# T35_4_FX3.net
KiCad netlist of a schematic drawn in Altium Designer
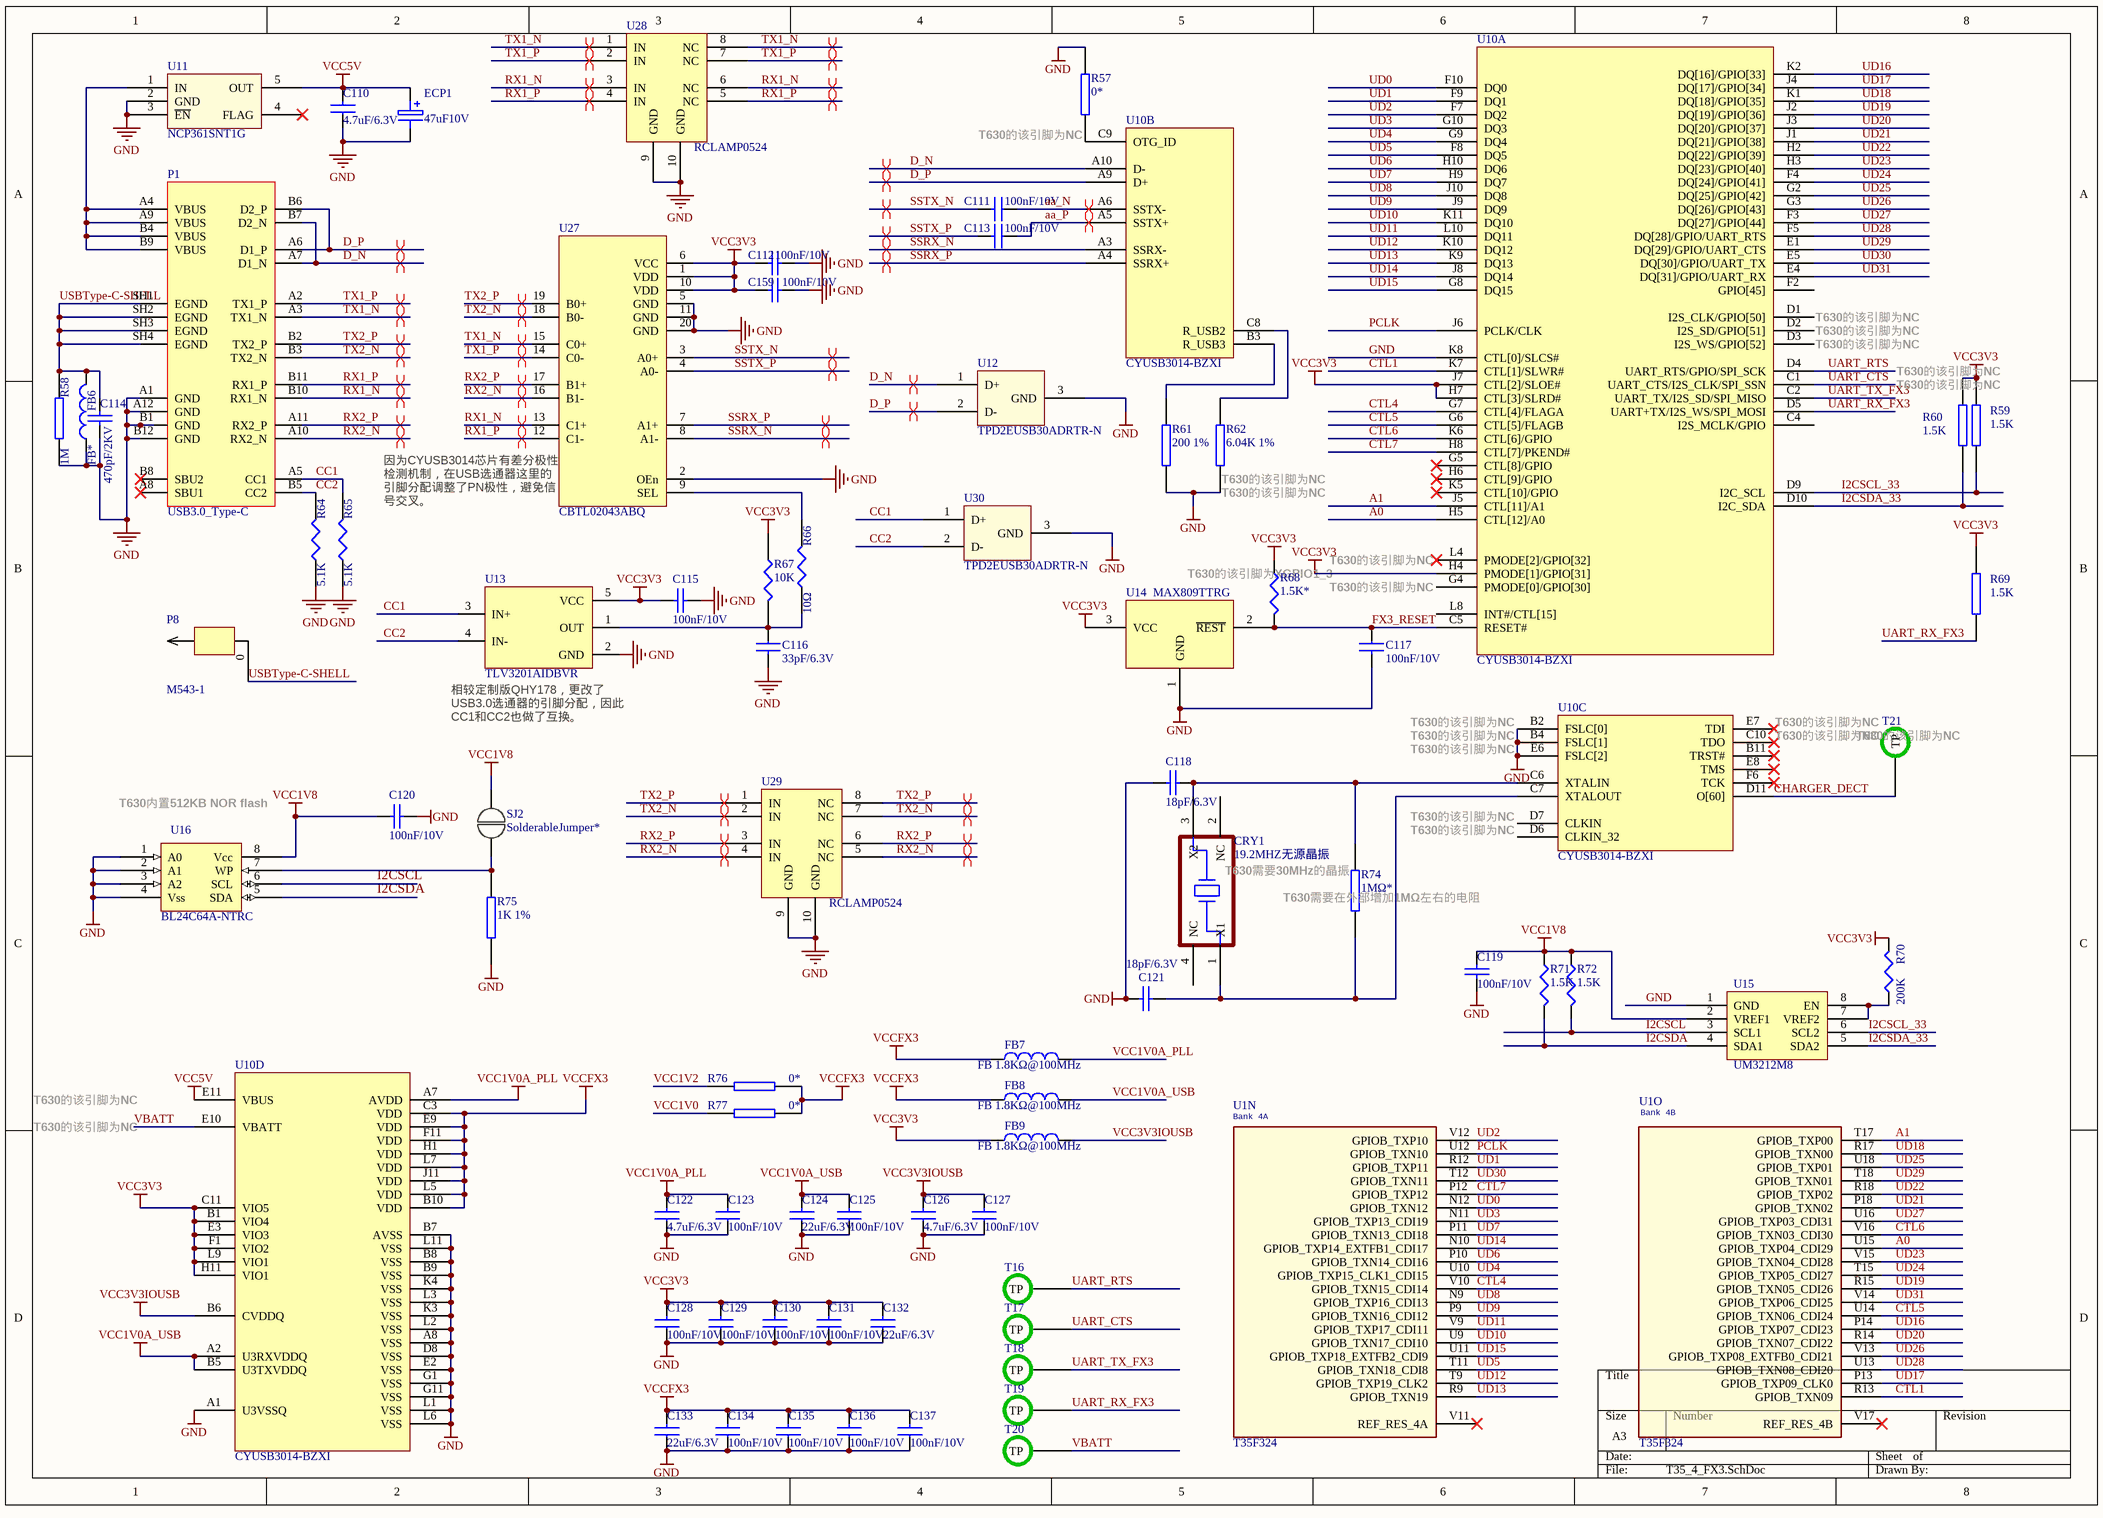
[diagram p0: T35_4_FX3.SchDoc]

(export (version "E")
  (design (tool "Eeschema 10.0.6"))
  (components
    (comp (ref "C110")
      (value "4.7uF/6.3V")
      (footprint "0402CS")
      (description "贴片电容")
      (libsource (lib "*") (part "CAPACITOR NON-POL"))
    )
    (comp (ref "C111")
      (value "100nF/10V")
      (footprint "0201CS")
      (description "贴片电容")
      (libsource (lib "*") (part "CAPACITOR NON-POL"))
    )
    (comp (ref "C112")
      (value "100nF/10V")
      (footprint "0201CS")
      (description "贴片电容")
      (libsource (lib "*") (part "CAP"))
    )
    (comp (ref "C113")
      (value "100nF/10V")
      (footprint "0201CS")
      (description "贴片电容")
      (libsource (lib "*") (part "CAPACITOR NON-POL"))
    )
    (comp (ref "C114")
      (value "470pF/2KV")
      (footprint "1206CS")
      (description "贴片电容")
      (libsource (lib "*") (part "CAP"))
    )
    (comp (ref "C115")
      (value "100nF/10V")
      (footprint "0201CS")
      (description "贴片电容")
      (libsource (lib "*") (part "CAP"))
    )
    (comp (ref "C116")
      (value "33pF/6.3V")
      (footprint "0402CS")
      (description "贴片电容")
      (libsource (lib "*") (part "CAPACITOR NON-POL"))
    )
    (comp (ref "C117")
      (value "100nF/10V")
      (footprint "0201CS")
      (description "贴片电容")
      (libsource (lib "*") (part "CAPACITOR NON-POL"))
    )
    (comp (ref "C118")
      (value "18pF/6.3V")
      (footprint "0201CS")
      (description "贴片电容")
      (libsource (lib "*") (part "CAP"))
    )
    (comp (ref "C119")
      (value "100nF/10V")
      (footprint "0201CS")
      (description "贴片电容")
      (libsource (lib "*") (part "CAP"))
    )
    (comp (ref "C120")
      (value "100nF/10V")
      (footprint "0201CS")
      (description "贴片电容")
      (libsource (lib "*") (part "CAP"))
    )
    (comp (ref "C121")
      (value "18pF/6.3V")
      (footprint "0201CS")
      (description "贴片电容")
      (libsource (lib "*") (part "CAP"))
    )
    (comp (ref "C122")
      (value "4.7uF/6.3V")
      (footprint "0402CS")
      (description "贴片电容")
      (libsource (lib "*") (part "CAPACITOR NON-POL"))
    )
    (comp (ref "C123")
      (value "100nF/10V")
      (footprint "0201CS")
      (description "贴片电容")
      (libsource (lib "*") (part "CAPACITOR NON-POL"))
    )
    (comp (ref "C124")
      (value "22uF/6.3V")
      (footprint "0603CS")
      (description "贴片电容")
      (libsource (lib "*") (part "CAPACITOR NON-POL"))
    )
    (comp (ref "C125")
      (value "100nF/10V")
      (footprint "0201CS")
      (description "贴片电容")
      (libsource (lib "*") (part "CAPACITOR NON-POL"))
    )
    (comp (ref "C126")
      (value "4.7uF/6.3V")
      (footprint "0402CS")
      (description "贴片电容")
      (libsource (lib "*") (part "CAPACITOR NON-POL"))
    )
    (comp (ref "C127")
      (value "100nF/10V")
      (footprint "0201CS")
      (description "贴片电容")
      (libsource (lib "*") (part "CAPACITOR NON-POL"))
    )
    (comp (ref "C128")
      (value "100nF/10V")
      (footprint "0201CS")
      (description "贴片电容")
      (libsource (lib "*") (part "CAPACITOR NON-POL"))
    )
    (comp (ref "C129")
      (value "100nF/10V")
      (footprint "0201CS")
      (description "贴片电容")
      (libsource (lib "*") (part "CAPACITOR NON-POL"))
    )
    (comp (ref "C130")
      (value "100nF/10V")
      (footprint "0201CS")
      (description "贴片电容")
      (libsource (lib "*") (part "CAPACITOR NON-POL"))
    )
    (comp (ref "C131")
      (value "100nF/10V")
      (footprint "0201CS")
      (description "贴片电容")
      (libsource (lib "*") (part "CAPACITOR NON-POL"))
    )
    (comp (ref "C132")
      (value "22uF/6.3V")
      (footprint "0603CS")
      (description "贴片电容")
      (libsource (lib "*") (part "CAPACITOR NON-POL"))
    )
    (comp (ref "C133")
      (value "22uF/6.3V")
      (footprint "0603CS")
      (description "贴片电容")
      (libsource (lib "*") (part "CAPACITOR NON-POL"))
    )
    (comp (ref "C134")
      (value "100nF/10V")
      (footprint "0201CS")
      (description "贴片电容")
      (libsource (lib "*") (part "CAPACITOR NON-POL"))
    )
    (comp (ref "C135")
      (value "100nF/10V")
      (footprint "0201CS")
      (description "贴片电容")
      (libsource (lib "*") (part "CAPACITOR NON-POL"))
    )
    (comp (ref "C136")
      (value "100nF/10V")
      (footprint "0201CS")
      (description "贴片电容")
      (libsource (lib "*") (part "CAPACITOR NON-POL"))
    )
    (comp (ref "C137")
      (value "100nF/10V")
      (footprint "0201CS")
      (description "贴片电容")
      (libsource (lib "*") (part "CAPACITOR NON-POL"))
    )
    (comp (ref "C159")
      (value "100nF/10V")
      (footprint "0201CS")
      (description "贴片电容")
      (libsource (lib "*") (part "CAP"))
    )
    (comp (ref "CRY1")
      (value "19.2MHZ无源晶振")
      (footprint "XTAL_SMD_SMALL")
      (description "无源晶振")
      (libsource (lib "QHY_SCHLIB") (part "CRY-4S"))
    )
    (comp (ref "ECP1")
      (value "47uF10V")
      (footprint "CASE-B")
      (description "钽电容")
      (libsource (lib "QHY_LIB_SCH_AD10") (part "ELECTRO1"))
    )
    (comp (ref "FB6")
      (value "FB*")
      (footprint "FB0603")
      (description "贴片磁珠")
      (libsource (lib "QHY_LIB_SCH_AD10") (part "INDUCTOR"))
    )
    (comp (ref "FB7")
      (value "FB 1.8KΩ@100MHz")
      (footprint "FB0603")
      (description "贴片磁珠")
      (libsource (lib "Miscellaneous Devices") (part "Inductor"))
    )
    (comp (ref "FB8")
      (value "FB 1.8KΩ@100MHz")
      (footprint "FB0603")
      (description "贴片磁珠")
      (libsource (lib "Miscellaneous Devices") (part "Inductor"))
    )
    (comp (ref "FB9")
      (value "FB 1.8KΩ@100MHz")
      (footprint "FB0603")
      (description "贴片磁珠")
      (libsource (lib "Miscellaneous Devices") (part "Inductor"))
    )
    (comp (ref "P1")
      (value "USB3.0_Type-C")
      (footprint "CONN_105450-0101_MOL - duplicate")
      (description "USB Type-C连接器")
      (libsource (lib "IMX411_V1") (part "USB3.0_Type-C"))
    )
    (comp (ref "P8")
      (value "M543-1")
      (footprint "M543-1")
      (description "弹簧针")
      (libsource (lib "T35-V2") (part "M543-1"))
    )
    (comp (ref "R57")
      (value "0*")
      (footprint "0201RS")
      (description "贴片电阻")
      (libsource (lib "*") (part "RES2"))
    )
    (comp (ref "R58")
      (value "1M")
      (footprint "0603RS")
      (description "贴片电阻")
      (libsource (lib "") (part "RES2_1"))
    )
    (comp (ref "R59")
      (value "1.5K")
      (footprint "0402RS")
      (description "贴片电阻")
      (libsource (lib "*") (part "RES2"))
    )
    (comp (ref "R60")
      (value "1.5K")
      (footprint "0402RS")
      (description "贴片电阻")
      (libsource (lib "*") (part "RES2"))
    )
    (comp (ref "R61")
      (value "200 1%")
      (footprint "0402RS")
      (description "贴片电阻")
      (libsource (lib "") (part "RES2_1"))
    )
    (comp (ref "R62")
      (value "6.04K 1%")
      (footprint "0402RS")
      (description "贴片电阻")
      (libsource (lib "") (part "RES2_1"))
    )
    (comp (ref "R64")
      (value "5.1K")
      (footprint "0201RS")
      (description "贴片电阻")
      (libsource (lib "*") (part "RES1"))
    )
    (comp (ref "R65")
      (value "5.1K")
      (footprint "0201RS")
      (description "贴片电阻")
      (libsource (lib "*") (part "RES1"))
    )
    (comp (ref "R66")
      (value "10Ω")
      (footprint "0402RS")
      (description "贴片电阻")
      (libsource (lib "*") (part "RES1"))
    )
    (comp (ref "R67")
      (value "10K")
      (footprint "0201RS")
      (description "贴片电阻")
      (libsource (lib "*") (part "RES1"))
    )
    (comp (ref "R68")
      (value "1.5K*")
      (footprint "0402RS")
      (description "贴片电阻")
      (fields (field (name "PUBLISHER") "Altium Limited"))
      (libsource (lib "Miscellaneous Devices") (part "Res3"))
    )
    (comp (ref "R69")
      (value "1.5K")
      (footprint "0402RS")
      (description "贴片电阻")
      (libsource (lib "*") (part "RES2"))
    )
    (comp (ref "R70")
      (value "200K")
      (footprint "0201RS")
      (description "贴片电阻")
      (fields (field (name "PUBLISHER") "Altium Limited"))
      (libsource (lib "Miscellaneous Devices") (part "Res3"))
    )
    (comp (ref "R71")
      (value "1.5K")
      (footprint "0402RS")
      (description "贴片电阻")
      (fields (field (name "PUBLISHER") "Altium Limited"))
      (libsource (lib "Miscellaneous Devices") (part "Res3"))
    )
    (comp (ref "R72")
      (value "1.5K")
      (footprint "0402RS")
      (description "贴片电阻")
      (fields (field (name "PUBLISHER") "Altium Limited"))
      (libsource (lib "Miscellaneous Devices") (part "Res3"))
    )
    (comp (ref "R74")
      (value "1MΩ*")
      (footprint "0402RS")
      (description "贴片电阻")
      (libsource (lib "") (part "RES2_1"))
    )
    (comp (ref "R75")
      (value "1K 1%")
      (footprint "0402RS")
      (description "贴片电阻")
      (libsource (lib "") (part "RES2_1"))
    )
    (comp (ref "R76")
      (value "0*")
      (footprint "0402RS")
      (description "贴片电阻")
      (libsource (lib "") (part "RES2_1"))
    )
    (comp (ref "R77")
      (value "0*")
      (footprint "0402RS")
      (description "贴片电阻")
      (libsource (lib "") (part "RES2_1"))
    )
    (comp (ref "SJ2")
      (value "SolderableJumper*")
      (footprint "SJ")
      (libsource (lib "T35-V2") (part "SolderableJumper"))
    )
    (comp (ref "T16")
      (value "~")
      (footprint "TP-S")
      (description "测试点")
      (libsource (lib "QHY_SCHLIB") (part "TP"))
    )
    (comp (ref "T17")
      (value "~")
      (footprint "TP-S")
      (description "测试点")
      (libsource (lib "QHY_SCHLIB") (part "TP"))
    )
    (comp (ref "T18")
      (value "~")
      (footprint "TP-S")
      (description "测试点")
      (libsource (lib "QHY_SCHLIB") (part "TP"))
    )
    (comp (ref "T19")
      (value "~")
      (footprint "TP-S")
      (description "测试点")
      (libsource (lib "QHY_SCHLIB") (part "TP"))
    )
    (comp (ref "T20")
      (value "~")
      (footprint "TP-S")
      (description "测试点")
      (libsource (lib "QHY_SCHLIB") (part "TP"))
    )
    (comp (ref "T21")
      (value "~")
      (footprint "TP-S")
      (description "测试点")
      (libsource (lib "QHY_SCHLIB") (part "TP"))
    )
    (comp (ref "U1")
      (value "T35F324")
      (footprint "T35-F324-BGA100P9X9-81A")
      (description "FPGA芯片")
      (libsource (lib "orcadt35-v1.0_Library") (part "T35F324"))
    )
    (comp (ref "U10")
      (value "CYUSB3014-BZXI")
      (footprint "CYUSB3014")
      (description "FX3芯片")
      (libsource (lib "QHY_SCHLIB") (part "CYUSB3014"))
    )
    (comp (ref "U11")
      (value "NCP361SNT1G")
      (footprint "SOT-23-5")
      (description "USB过压过流保护芯片")
      (libsource (lib "T35-V2") (part "NCP361SNT1G"))
    )
    (comp (ref "U12")
      (value "TPD2EUSB30ADRTR-N")
      (footprint "DRT0003A")
      (description "ESD保护器件")
      (libsource (lib "T35-V2") (part "TPD2EUSB30ADRTR-N"))
    )
    (comp (ref "U13")
      (value "TLV3201AIDBVR")
      (footprint "sot-23-5")
      (description "比较器")
      (libsource (lib "IMX411_V1") (part "TLV3201AIDBVR"))
    )
    (comp (ref "U14")
      (value "MAX809TTRG")
      (footprint "MAX809")
      (description "复位芯片")
      (libsource (lib "QHY_SCHLIB") (part "MAX809"))
    )
    (comp (ref "U15")
      (value "UM3212M8")
      (footprint "MSOP8")
      (description "I2C电平转换芯片")
      (libsource (lib "QHY_LIB_SCH_AD10") (part "UM3212M8"))
    )
    (comp (ref "U16")
      (value "BL24C64A-NTRC")
      (footprint "UDFN-8LL")
      (description "EEPROM芯片")
      (libsource (lib "*") (part "24LC00"))
    )
    (comp (ref "U27")
      (value "CBTL02043ABQ")
      (footprint "VQFN-20")
      (description "USB3.0选通芯片")
      (libsource (lib "T35-V2") (part "CBTL02043ABQ"))
    )
    (comp (ref "U28")
      (value "RCLAMP0524")
      (footprint "RCLAMP0524")
      (description "ESD保护器件")
      (libsource (lib "QHY_SCHLIB") (part "RCLAMP0524"))
    )
    (comp (ref "U29")
      (value "RCLAMP0524")
      (footprint "RCLAMP0524")
      (description "ESD保护器件")
      (libsource (lib "QHY_SCHLIB") (part "RCLAMP0524"))
    )
    (comp (ref "U30")
      (value "TPD2EUSB30ADRTR-N")
      (footprint "DRT0003A")
      (description "ESD保护器件")
      (libsource (lib "T35-V2") (part "TPD2EUSB30ADRTR-N"))
    )
  )
  (nets
    (net (code "1") (name "/A0") (class "Default")
      (node (ref "U1") (pin "U15") (pinfunction "GPIOB_TXP04_CDI29_U15") (pintype "power_in"))
      (node (ref "U10") (pin "H5") (pinfunction "CTL[12]/A0_H5") (pintype "passive"))
    )
    (net (code "2") (name "/A1") (class "Default")
      (node (ref "U1") (pin "T17") (pinfunction "GPIOB_TXP00_T17") (pintype "power_in"))
      (node (ref "U10") (pin "J5") (pinfunction "CTL[11]/A1_J5") (pintype "passive"))
    )
    (net (code "3") (name "/CC1") (class "Default")
      (node (ref "P1") (pin "A5") (pinfunction "CC1_A5") (pintype "passive"))
      (node (ref "R65") (pin "2") (pinfunction "2_2") (pintype "passive"))
      (node (ref "U13") (pin "3") (pinfunction "IN+_3") (pintype "passive"))
      (node (ref "U30") (pin "1") (pinfunction "D+_1") (pintype "passive"))
    )
    (net (code "4") (name "/CC2") (class "Default")
      (node (ref "P1") (pin "B5") (pinfunction "CC2_B5") (pintype "passive"))
      (node (ref "R64") (pin "2") (pinfunction "2_2") (pintype "passive"))
      (node (ref "U13") (pin "4") (pinfunction "IN-_4") (pintype "passive"))
      (node (ref "U30") (pin "2") (pinfunction "D-_2") (pintype "passive"))
    )
    (net (code "5") (name "/CHARGER_DECT") (class "Default")
      (node (ref "T21") (pin "1") (pinfunction "TP_1") (pintype "passive"))
      (node (ref "U10") (pin "D11") (pinfunction "O[60]_D11") (pintype "passive"))
    )
    (net (code "6") (name "/CTL1") (class "Default")
      (node (ref "U1") (pin "R13") (pinfunction "GPIOB_TXN09_R13") (pintype "power_in"))
      (node (ref "U10") (pin "K7") (pinfunction "CTL[1]/SLWR#_K7") (pintype "passive"))
    )
    (net (code "7") (name "/CTL4") (class "Default")
      (node (ref "U1") (pin "V10") (pinfunction "GPIOB_TXN15_CDI14_V10") (pintype "passive"))
      (node (ref "U10") (pin "G7") (pinfunction "CTL[4]/FLAGA_G7") (pintype "passive"))
    )
    (net (code "8") (name "/CTL5") (class "Default")
      (node (ref "U1") (pin "U14") (pinfunction "GPIOB_TXN06_CDI24_U14") (pintype "power_in"))
      (node (ref "U10") (pin "G6") (pinfunction "CTL[5]/FLAGB_G6") (pintype "passive"))
    )
    (net (code "9") (name "/CTL6") (class "Default")
      (node (ref "U1") (pin "V16") (pinfunction "GPIOB_TXN03_CDI30_V16") (pintype "power_in"))
      (node (ref "U10") (pin "K6") (pinfunction "CTL[6]/GPIO_K6") (pintype "passive"))
    )
    (net (code "10") (name "/CTL7") (class "Default")
      (node (ref "U1") (pin "P12") (pinfunction "GPIOB_TXP12_P12") (pintype "passive"))
      (node (ref "U10") (pin "H8") (pinfunction "CTL[7]/PKEND#_H8") (pintype "passive"))
    )
    (net (code "11") (name "/D_N") (class "Default")
      (node (ref "P1") (pin "A7") (pinfunction "D1_N_A7") (pintype "passive"))
      (node (ref "P1") (pin "B7") (pinfunction "D2_N_B7") (pintype "passive"))
      (node (ref "U10") (pin "A10") (pinfunction "D-_A10") (pintype "passive"))
      (node (ref "U12") (pin "1") (pinfunction "D+_1") (pintype "passive"))
    )
    (net (code "12") (name "/D_P") (class "Default")
      (node (ref "P1") (pin "A6") (pinfunction "D1_P_A6") (pintype "passive"))
      (node (ref "P1") (pin "B6") (pinfunction "D2_P_B6") (pintype "passive"))
      (node (ref "U10") (pin "A9") (pinfunction "D+_A9") (pintype "passive"))
      (node (ref "U12") (pin "2") (pinfunction "D-_2") (pintype "passive"))
    )
    (net (code "13") (name "/FX3_RESET") (class "Default")
      (node (ref "C117") (pin "1") (pinfunction "1_1") (pintype "passive"))
      (node (ref "R68") (pin "2") (pinfunction "2_2") (pintype "passive"))
      (node (ref "U10") (pin "C5") (pinfunction "RESET#_C5") (pintype "passive"))
      (node (ref "U14") (pin "2") (pinfunction "~{REST}_2") (pintype "passive"))
    )
    (net (code "14") (name "/I2CSCL") (class "Default")
      (node (ref "R72") (pin "2") (pinfunction "2_2") (pintype "passive"))
      (node (ref "U15") (pin "3") (pinfunction "SCL1_3") (pintype "passive"))
      (node (ref "U16") (pin "6") (pinfunction "SCL_6") (pintype "bidirectional"))
    )
    (net (code "15") (name "/I2CSCL_33") (class "Default")
      (node (ref "R59") (pin "2") (pinfunction "2_2") (pintype "passive"))
      (node (ref "U10") (pin "D9") (pinfunction "I2C_SCL_D9") (pintype "passive"))
      (node (ref "U15") (pin "6") (pinfunction "SCL2_6") (pintype "passive"))
    )
    (net (code "16") (name "/I2CSDA") (class "Default")
      (node (ref "R71") (pin "2") (pinfunction "2_2") (pintype "passive"))
      (node (ref "U15") (pin "4") (pinfunction "SDA1_4") (pintype "passive"))
      (node (ref "U16") (pin "5") (pinfunction "SDA_5") (pintype "bidirectional"))
    )
    (net (code "17") (name "/I2CSDA_33") (class "Default")
      (node (ref "R60") (pin "2") (pinfunction "2_2") (pintype "passive"))
      (node (ref "U10") (pin "D10") (pinfunction "I2C_SDA_D10") (pintype "passive"))
      (node (ref "U15") (pin "5") (pinfunction "SDA2_5") (pintype "passive"))
    )
    (net (code "18") (name "/PCLK") (class "Default")
      (node (ref "U1") (pin "U12") (pinfunction "GPIOB_TXN10_U12") (pintype "passive"))
      (node (ref "U10") (pin "J6") (pinfunction "PCLK/CLK_J6") (pintype "passive"))
    )
    (net (code "19") (name "/RX1_N") (class "Default")
      (node (ref "P1") (pin "B10") (pinfunction "RX1_N_B10") (pintype "passive"))
      (node (ref "U27") (pin "13") (pinfunction "C1+_13") (pintype "passive"))
      (node (ref "U28") (pin "3") (pinfunction "IN_3") (pintype "passive"))
      (node (ref "U28") (pin "6") (pinfunction "NC_6") (pintype "passive"))
    )
    (net (code "20") (name "/RX1_P") (class "Default")
      (node (ref "P1") (pin "B11") (pinfunction "RX1_P_B11") (pintype "passive"))
      (node (ref "U27") (pin "12") (pinfunction "C1-_12") (pintype "passive"))
      (node (ref "U28") (pin "4") (pinfunction "IN_4") (pintype "passive"))
      (node (ref "U28") (pin "5") (pinfunction "NC_5") (pintype "passive"))
    )
    (net (code "21") (name "/RX2_N") (class "Default")
      (node (ref "P1") (pin "A10") (pinfunction "RX2_N_A10") (pintype "passive"))
      (node (ref "U27") (pin "16") (pinfunction "B1-_16") (pintype "passive"))
      (node (ref "U29") (pin "4") (pinfunction "IN_4") (pintype "passive"))
      (node (ref "U29") (pin "5") (pinfunction "NC_5") (pintype "passive"))
    )
    (net (code "22") (name "/RX2_P") (class "Default")
      (node (ref "P1") (pin "A11") (pinfunction "RX2_P_A11") (pintype "passive"))
      (node (ref "U27") (pin "17") (pinfunction "B1+_17") (pintype "passive"))
      (node (ref "U29") (pin "3") (pinfunction "IN_3") (pintype "passive"))
      (node (ref "U29") (pin "6") (pinfunction "NC_6") (pintype "passive"))
    )
    (net (code "23") (name "/SSRX_N") (class "Default")
      (node (ref "U10") (pin "A3") (pinfunction "SSRX-_A3") (pintype "passive"))
      (node (ref "U27") (pin "8") (pinfunction "A1-_8") (pintype "passive"))
    )
    (net (code "24") (name "/SSRX_P") (class "Default")
      (node (ref "U10") (pin "A4") (pinfunction "SSRX+_A4") (pintype "passive"))
      (node (ref "U27") (pin "7") (pinfunction "A1+_7") (pintype "passive"))
    )
    (net (code "25") (name "/SSTX_N") (class "Default")
      (node (ref "C111") (pin "2") (pinfunction "2_2") (pintype "passive"))
      (node (ref "U27") (pin "3") (pinfunction "A0+_3") (pintype "passive"))
    )
    (net (code "26") (name "/SSTX_P") (class "Default")
      (node (ref "C113") (pin "2") (pinfunction "2_2") (pintype "passive"))
      (node (ref "U27") (pin "4") (pinfunction "A0-_4") (pintype "passive"))
    )
    (net (code "27") (name "/TX1_N") (class "Default")
      (node (ref "P1") (pin "A3") (pinfunction "TX1_N_A3") (pintype "passive"))
      (node (ref "U27") (pin "15") (pinfunction "C0+_15") (pintype "passive"))
      (node (ref "U28") (pin "1") (pinfunction "IN_1") (pintype "passive"))
      (node (ref "U28") (pin "8") (pinfunction "NC_8") (pintype "passive"))
    )
    (net (code "28") (name "/TX1_P") (class "Default")
      (node (ref "P1") (pin "A2") (pinfunction "TX1_P_A2") (pintype "passive"))
      (node (ref "U27") (pin "14") (pinfunction "C0-_14") (pintype "passive"))
      (node (ref "U28") (pin "2") (pinfunction "IN_2") (pintype "passive"))
      (node (ref "U28") (pin "7") (pinfunction "NC_7") (pintype "passive"))
    )
    (net (code "29") (name "/TX2_N") (class "Default")
      (node (ref "P1") (pin "B3") (pinfunction "TX2_N_B3") (pintype "passive"))
      (node (ref "U27") (pin "18") (pinfunction "B0-_18") (pintype "passive"))
      (node (ref "U29") (pin "2") (pinfunction "IN_2") (pintype "passive"))
      (node (ref "U29") (pin "7") (pinfunction "NC_7") (pintype "passive"))
    )
    (net (code "30") (name "/TX2_P") (class "Default")
      (node (ref "P1") (pin "B2") (pinfunction "TX2_P_B2") (pintype "passive"))
      (node (ref "U27") (pin "19") (pinfunction "B0+_19") (pintype "passive"))
      (node (ref "U29") (pin "1") (pinfunction "IN_1") (pintype "passive"))
      (node (ref "U29") (pin "8") (pinfunction "NC_8") (pintype "passive"))
    )
    (net (code "31") (name "/UART_CTS") (class "Default")
      (node (ref "T17") (pin "1") (pinfunction "TP_1") (pintype "passive"))
      (node (ref "U10") (pin "C1") (pinfunction "UART_CTS/I2S_CLK/SPI_SSN_C1") (pintype "passive"))
    )
    (net (code "32") (name "/UART_RTS") (class "Default")
      (node (ref "T16") (pin "1") (pinfunction "TP_1") (pintype "passive"))
      (node (ref "U10") (pin "D4") (pinfunction "UART_RTS/GPIO/SPI_SCK_D4") (pintype "passive"))
    )
    (net (code "33") (name "/UART_RX_FX3") (class "Default")
      (node (ref "R69") (pin "2") (pinfunction "2_2") (pintype "passive"))
      (node (ref "T19") (pin "1") (pinfunction "TP_1") (pintype "passive"))
      (node (ref "U10") (pin "D5") (pinfunction "UART+TX/I2S_WS/SPI_MOSI_D5") (pintype "passive"))
    )
    (net (code "34") (name "/UART_TX_FX3") (class "Default")
      (node (ref "T18") (pin "1") (pinfunction "TP_1") (pintype "passive"))
      (node (ref "U10") (pin "C2") (pinfunction "UART_TX/I2S_SD/SPI_MISO_C2") (pintype "passive"))
    )
    (net (code "35") (name "/UD0") (class "Default")
      (node (ref "U1") (pin "N12") (pinfunction "GPIOB_TXN12_N12") (pintype "passive"))
      (node (ref "U10") (pin "F10") (pinfunction "DQ0_F10") (pintype "passive"))
    )
    (net (code "36") (name "/UD1") (class "Default")
      (node (ref "U1") (pin "R12") (pinfunction "GPIOB_TXP11_R12") (pintype "passive"))
      (node (ref "U10") (pin "F9") (pinfunction "DQ1_F9") (pintype "passive"))
    )
    (net (code "37") (name "/UD2") (class "Default")
      (node (ref "U1") (pin "V12") (pinfunction "GPIOB_TXP10_V12") (pintype "passive"))
      (node (ref "U10") (pin "F7") (pinfunction "DQ2_F7") (pintype "passive"))
    )
    (net (code "38") (name "/UD3") (class "Default")
      (node (ref "U1") (pin "N11") (pinfunction "GPIOB_TXP13_CDI19_N11") (pintype "passive"))
      (node (ref "U10") (pin "G10") (pinfunction "DQ3_G10") (pintype "passive"))
    )
    (net (code "39") (name "/UD4") (class "Default")
      (node (ref "U1") (pin "U10") (pinfunction "GPIOB_TXP15_CLK1_CDI15_U10") (pintype "power_in"))
      (node (ref "U10") (pin "G9") (pinfunction "DQ4_G9") (pintype "passive"))
    )
    (net (code "40") (name "/UD5") (class "Default")
      (node (ref "U1") (pin "T11") (pinfunction "GPIOB_TXN18_CDI8_T11") (pintype "passive"))
      (node (ref "U10") (pin "F8") (pinfunction "DQ5_F8") (pintype "passive"))
    )
    (net (code "41") (name "/UD6") (class "Default")
      (node (ref "U1") (pin "P10") (pinfunction "GPIOB_TXN14_CDI16_P10") (pintype "passive"))
      (node (ref "U10") (pin "H10") (pinfunction "DQ6_H10") (pintype "passive"))
    )
    (net (code "42") (name "/UD7") (class "Default")
      (node (ref "U1") (pin "P11") (pinfunction "GPIOB_TXN13_CDI18_P11") (pintype "passive"))
      (node (ref "U10") (pin "H9") (pinfunction "DQ7_H9") (pintype "passive"))
    )
    (net (code "43") (name "/UD8") (class "Default")
      (node (ref "U1") (pin "N9") (pinfunction "GPIOB_TXP16_CDI13_N9") (pintype "power_in"))
      (node (ref "U10") (pin "J10") (pinfunction "DQ8_J10") (pintype "passive"))
    )
    (net (code "44") (name "/UD9") (class "Default")
      (node (ref "U1") (pin "P9") (pinfunction "GPIOB_TXN16_CDI12_P9") (pintype "passive"))
      (node (ref "U10") (pin "J9") (pinfunction "DQ9_J9") (pintype "passive"))
    )
    (net (code "45") (name "/UD10") (class "Default")
      (node (ref "U1") (pin "U9") (pinfunction "GPIOB_TXN17_CDI10_U9") (pintype "passive"))
      (node (ref "U10") (pin "K11") (pinfunction "DQ10_K11") (pintype "passive"))
    )
    (net (code "46") (name "/UD11") (class "Default")
      (node (ref "U1") (pin "V9") (pinfunction "GPIOB_TXP17_CDI11_V9") (pintype "power_in"))
      (node (ref "U10") (pin "L10") (pinfunction "DQ11_L10") (pintype "passive"))
    )
    (net (code "47") (name "/UD12") (class "Default")
      (node (ref "U1") (pin "T9") (pinfunction "GPIOB_TXP19_CLK2_T9") (pintype "power_in"))
      (node (ref "U10") (pin "K10") (pinfunction "DQ12_K10") (pintype "passive"))
    )
    (net (code "48") (name "/UD13") (class "Default")
      (node (ref "U1") (pin "R9") (pinfunction "GPIOB_TXN19_R9") (pintype "passive"))
      (node (ref "U10") (pin "K9") (pinfunction "DQ13_K9") (pintype "passive"))
    )
    (net (code "49") (name "/UD14") (class "Default")
      (node (ref "U1") (pin "N10") (pinfunction "GPIOB_TXP14_EXTFB1_CDI17_N10") (pintype "passive"))
      (node (ref "U10") (pin "J8") (pinfunction "DQ14_J8") (pintype "passive"))
    )
    (net (code "50") (name "/UD15") (class "Default")
      (node (ref "U1") (pin "U11") (pinfunction "GPIOB_TXP18_EXTFB2_CDI9_U11") (pintype "power_in"))
      (node (ref "U10") (pin "G8") (pinfunction "DQ15_G8") (pintype "passive"))
    )
    (net (code "51") (name "/UD16") (class "Default")
      (node (ref "U1") (pin "P14") (pinfunction "GPIOB_TXP07_CDI23_P14") (pintype "power_in"))
      (node (ref "U10") (pin "K2") (pinfunction "DQ[16]/GPIO[33]_K2") (pintype "passive"))
    )
    (net (code "52") (name "/UD17") (class "Default")
      (node (ref "U1") (pin "P13") (pinfunction "GPIOB_TXP09_CLK0_P13") (pintype "power_in"))
      (node (ref "U10") (pin "J4") (pinfunction "DQ[17]/GPIO[34]_J4") (pintype "passive"))
    )
    (net (code "53") (name "/UD18") (class "Default")
      (node (ref "U1") (pin "R17") (pinfunction "GPIOB_TXN00_R17") (pintype "power_in"))
      (node (ref "U10") (pin "K1") (pinfunction "DQ[18]/GPIO[35]_K1") (pintype "passive"))
    )
    (net (code "54") (name "/UD19") (class "Default")
      (node (ref "U1") (pin "R15") (pinfunction "GPIOB_TXN05_CDI26_R15") (pintype "power_in"))
      (node (ref "U10") (pin "J2") (pinfunction "DQ[19]/GPIO[36]_J2") (pintype "passive"))
    )
    (net (code "55") (name "/UD20") (class "Default")
      (node (ref "U1") (pin "R14") (pinfunction "GPIOB_TXN07_CDI22_R14") (pintype "power_in"))
      (node (ref "U10") (pin "J3") (pinfunction "DQ[20]/GPIO[37]_J3") (pintype "passive"))
    )
    (net (code "56") (name "/UD21") (class "Default")
      (node (ref "U1") (pin "P18") (pinfunction "GPIOB_TXN02_P18") (pintype "power_in"))
      (node (ref "U10") (pin "J1") (pinfunction "DQ[21]/GPIO[38]_J1") (pintype "passive"))
    )
    (net (code "57") (name "/UD22") (class "Default")
      (node (ref "U1") (pin "R18") (pinfunction "GPIOB_TXP02_R18") (pintype "power_in"))
      (node (ref "U10") (pin "H2") (pinfunction "DQ[22]/GPIO[39]_H2") (pintype "passive"))
    )
    (net (code "58") (name "/UD23") (class "Default")
      (node (ref "U1") (pin "V15") (pinfunction "GPIOB_TXN04_CDI28_V15") (pintype "power_in"))
      (node (ref "U10") (pin "H3") (pinfunction "DQ[23]/GPIO[40]_H3") (pintype "passive"))
    )
    (net (code "59") (name "/UD24") (class "Default")
      (node (ref "U1") (pin "T15") (pinfunction "GPIOB_TXP05_CDI27_T15") (pintype "power_in"))
      (node (ref "U10") (pin "F4") (pinfunction "DQ[24]/GPIO[41]_F4") (pintype "passive"))
    )
    (net (code "60") (name "/UD25") (class "Default")
      (node (ref "U1") (pin "U18") (pinfunction "GPIOB_TXP01_U18") (pintype "power_in"))
      (node (ref "U10") (pin "G2") (pinfunction "DQ[25]/GPIO[42]_G2") (pintype "passive"))
    )
    (net (code "61") (name "/UD26") (class "Default")
      (node (ref "U1") (pin "V13") (pinfunction "GPIOB_TXP08_EXTFB0_CDI21_V13") (pintype "power_in"))
      (node (ref "U10") (pin "G3") (pinfunction "DQ[26]/GPIO[43]_G3") (pintype "passive"))
    )
    (net (code "62") (name "/UD27") (class "Default")
      (node (ref "U1") (pin "U16") (pinfunction "GPIOB_TXP03_CDI31_U16") (pintype "power_in"))
      (node (ref "U10") (pin "F3") (pinfunction "DQ[27]/GPIO[44]_F3") (pintype "passive"))
    )
    (net (code "63") (name "/UD28") (class "Default")
      (node (ref "U1") (pin "U13") (pinfunction "GPIOB_TXN08_CDI20_U13") (pintype "power_in"))
      (node (ref "U10") (pin "F5") (pinfunction "DQ[28]/GPIO/UART_RTS_F5") (pintype "passive"))
    )
    (net (code "64") (name "/UD29") (class "Default")
      (node (ref "U1") (pin "T18") (pinfunction "GPIOB_TXN01_T18") (pintype "power_in"))
      (node (ref "U10") (pin "E1") (pinfunction "DQ[29]/GPIO/UART_CTS_E1") (pintype "passive"))
    )
    (net (code "65") (name "/UD30") (class "Default")
      (node (ref "U1") (pin "T12") (pinfunction "GPIOB_TXN11_T12") (pintype "passive"))
      (node (ref "U10") (pin "E5") (pinfunction "DQ[30]/GPIO/UART_TX_E5") (pintype "passive"))
    )
    (net (code "66") (name "/UD31") (class "Default")
      (node (ref "U1") (pin "V14") (pinfunction "GPIOB_TXP06_CDI25_V14") (pintype "power_in"))
      (node (ref "U10") (pin "E4") (pinfunction "DQ[31]/GPIO/UART_RX_E4") (pintype "passive"))
    )
    (net (code "67") (name "/USBType-C-SHELL") (class "Default")
      (node (ref "C114") (pin "2") (pinfunction "2_2") (pintype "passive"))
      (node (ref "FB6") (pin "2") (pinfunction "2_2") (pintype "passive"))
      (node (ref "P1") (pin "SH1") (pinfunction "EGND_SH1") (pintype "passive"))
      (node (ref "P1") (pin "SH2") (pinfunction "EGND_SH2") (pintype "passive"))
      (node (ref "P1") (pin "SH3") (pinfunction "EGND_SH3") (pintype "passive"))
      (node (ref "P1") (pin "SH4") (pinfunction "EGND_SH4") (pintype "passive"))
      (node (ref "P8") (pin "0") (pinfunction "0_0") (pintype "passive"))
      (node (ref "R58") (pin "1") (pinfunction "1_1") (pintype "passive"))
    )
    (net (code "68") (name "/VBATT") (class "Default")
      (node (ref "T20") (pin "1") (pinfunction "TP_1") (pintype "passive"))
      (node (ref "U10") (pin "E10") (pinfunction "VBATT_E10") (pintype "passive"))
    )
    (net (code "69") (name "/VCC1V0") (class "Default")
      (node (ref "R77") (pin "2") (pinfunction "2_2") (pintype "passive"))
    )
    (net (code "70") (name "/VCC1V2") (class "Default")
      (node (ref "R76") (pin "2") (pinfunction "2_2") (pintype "passive"))
    )
    (net (code "71") (name "/aa_N") (class "Default")
      (node (ref "C111") (pin "1") (pinfunction "1_1") (pintype "passive"))
      (node (ref "U10") (pin "A6") (pinfunction "SSTX-_A6") (pintype "passive"))
    )
    (net (code "72") (name "/aa_P") (class "Default")
      (node (ref "C113") (pin "1") (pinfunction "1_1") (pintype "passive"))
      (node (ref "U10") (pin "A5") (pinfunction "SSTX+_A5") (pintype "passive"))
    )
    (net (code "73") (name "GND") (class "Default")
      (node (ref "C110") (pin "1") (pinfunction "1_1") (pintype "passive"))
      (node (ref "C112") (pin "1") (pinfunction "1_1") (pintype "passive"))
      (node (ref "C114") (pin "1") (pinfunction "1_1") (pintype "passive"))
      (node (ref "C115") (pin "1") (pinfunction "1_1") (pintype "passive"))
      (node (ref "C116") (pin "2") (pinfunction "2_2") (pintype "passive"))
      (node (ref "C117") (pin "2") (pinfunction "2_2") (pintype "passive"))
      (node (ref "C118") (pin "1") (pinfunction "1_1") (pintype "passive"))
      (node (ref "C119") (pin "2") (pinfunction "2_2") (pintype "passive"))
      (node (ref "C120") (pin "1") (pinfunction "1_1") (pintype "passive"))
      (node (ref "C121") (pin "2") (pinfunction "2_2") (pintype "passive"))
      (node (ref "C122") (pin "1") (pinfunction "1_1") (pintype "passive"))
      (node (ref "C123") (pin "1") (pinfunction "1_1") (pintype "passive"))
      (node (ref "C124") (pin "1") (pinfunction "1_1") (pintype "passive"))
      (node (ref "C125") (pin "1") (pinfunction "1_1") (pintype "passive"))
      (node (ref "C126") (pin "1") (pinfunction "1_1") (pintype "passive"))
      (node (ref "C127") (pin "1") (pinfunction "1_1") (pintype "passive"))
      (node (ref "C128") (pin "1") (pinfunction "1_1") (pintype "passive"))
      (node (ref "C129") (pin "1") (pinfunction "1_1") (pintype "passive"))
      (node (ref "C130") (pin "1") (pinfunction "1_1") (pintype "passive"))
      (node (ref "C131") (pin "1") (pinfunction "1_1") (pintype "passive"))
      (node (ref "C132") (pin "1") (pinfunction "1_1") (pintype "passive"))
      (node (ref "C133") (pin "1") (pinfunction "1_1") (pintype "passive"))
      (node (ref "C134") (pin "1") (pinfunction "1_1") (pintype "passive"))
      (node (ref "C135") (pin "1") (pinfunction "1_1") (pintype "passive"))
      (node (ref "C136") (pin "1") (pinfunction "1_1") (pintype "passive"))
      (node (ref "C137") (pin "1") (pinfunction "1_1") (pintype "passive"))
      (node (ref "C159") (pin "1") (pinfunction "1_1") (pintype "passive"))
      (node (ref "ECP1") (pin "2") (pinfunction "2_2") (pintype "passive"))
      (node (ref "FB6") (pin "1") (pinfunction "1_1") (pintype "passive"))
      (node (ref "P1") (pin "A1") (pinfunction "GND_A1") (pintype "passive"))
      (node (ref "P1") (pin "A12") (pinfunction "GND_A12") (pintype "passive"))
      (node (ref "P1") (pin "B1") (pinfunction "GND_B1") (pintype "passive"))
      (node (ref "P1") (pin "B12") (pinfunction "GND_B12") (pintype "passive"))
      (node (ref "R57") (pin "1") (pinfunction "1_1") (pintype "passive"))
      (node (ref "R58") (pin "2") (pinfunction "2_2") (pintype "passive"))
      (node (ref "R61") (pin "2") (pinfunction "2_2") (pintype "passive"))
      (node (ref "R62") (pin "2") (pinfunction "2_2") (pintype "passive"))
      (node (ref "R64") (pin "1") (pinfunction "1_1") (pintype "passive"))
      (node (ref "R65") (pin "1") (pinfunction "1_1") (pintype "passive"))
      (node (ref "R75") (pin "2") (pinfunction "2_2") (pintype "passive"))
      (node (ref "U10") (pin "A1") (pinfunction "U3VSSQ_A1") (pintype "passive"))
      (node (ref "U10") (pin "A8") (pinfunction "VSS_A8") (pintype "passive"))
      (node (ref "U10") (pin "B2") (pinfunction "FSLC[0]_B2") (pintype "passive"))
      (node (ref "U10") (pin "B4") (pinfunction "FSLC[1]_B4") (pintype "passive"))
      (node (ref "U10") (pin "B7") (pinfunction "AVSS_B7") (pintype "passive"))
      (node (ref "U10") (pin "B8") (pinfunction "VSS_B8") (pintype "passive"))
      (node (ref "U10") (pin "B9") (pinfunction "VSS_B9") (pintype "passive"))
      (node (ref "U10") (pin "D8") (pinfunction "VSS_D8") (pintype "passive"))
      (node (ref "U10") (pin "E2") (pinfunction "VSS_E2") (pintype "passive"))
      (node (ref "U10") (pin "E6") (pinfunction "FSLC[2]_E6") (pintype "passive"))
      (node (ref "U10") (pin "G1") (pinfunction "VSS_G1") (pintype "passive"))
      (node (ref "U10") (pin "G11") (pinfunction "VSS_G11") (pintype "passive"))
      (node (ref "U10") (pin "K3") (pinfunction "VSS_K3") (pintype "passive"))
      (node (ref "U10") (pin "K4") (pinfunction "VSS_K4") (pintype "passive"))
      (node (ref "U10") (pin "K8") (pinfunction "CTL[0]/SLCS#_K8") (pintype "passive"))
      (node (ref "U10") (pin "L1") (pinfunction "VSS_L1") (pintype "passive"))
      (node (ref "U10") (pin "L11") (pinfunction "VSS_L11") (pintype "passive"))
      (node (ref "U10") (pin "L2") (pinfunction "VSS_L2") (pintype "passive"))
      (node (ref "U10") (pin "L3") (pinfunction "VSS_L3") (pintype "passive"))
      (node (ref "U10") (pin "L6") (pinfunction "VSS_L6") (pintype "passive"))
      (node (ref "U11") (pin "2") (pinfunction "GND_2") (pintype "passive"))
      (node (ref "U11") (pin "3") (pinfunction "~{EN}_3") (pintype "passive"))
      (node (ref "U12") (pin "3") (pinfunction "GND_3") (pintype "passive"))
      (node (ref "U13") (pin "2") (pinfunction "GND_2") (pintype "passive"))
      (node (ref "U14") (pin "1") (pinfunction "GND_1") (pintype "passive"))
      (node (ref "U15") (pin "1") (pinfunction "GND_1") (pintype "passive"))
      (node (ref "U16") (pin "1") (pinfunction "A0_1") (pintype "input"))
      (node (ref "U16") (pin "2") (pinfunction "A1_2") (pintype "input"))
      (node (ref "U16") (pin "3") (pinfunction "A2_3") (pintype "input"))
      (node (ref "U16") (pin "4") (pinfunction "Vss_4") (pintype "power_in"))
      (node (ref "U27") (pin "11") (pinfunction "GND_11") (pintype "passive"))
      (node (ref "U27") (pin "2") (pinfunction "OEn_2") (pintype "passive"))
      (node (ref "U27") (pin "20") (pinfunction "GND_20") (pintype "passive"))
      (node (ref "U27") (pin "5") (pinfunction "GND_5") (pintype "passive"))
      (node (ref "U28") (pin "10") (pinfunction "GND_10") (pintype "passive"))
      (node (ref "U28") (pin "9") (pinfunction "GND_9") (pintype "passive"))
      (node (ref "U29") (pin "10") (pinfunction "GND_10") (pintype "passive"))
      (node (ref "U29") (pin "9") (pinfunction "GND_9") (pintype "passive"))
      (node (ref "U30") (pin "3") (pinfunction "GND_3") (pintype "passive"))
    )
    (net (code "74") (name "Net-(CRY1-X1)") (class "Default")
      (node (ref "C121") (pin "1") (pinfunction "1_1") (pintype "passive"))
      (node (ref "CRY1") (pin "1") (pinfunction "X1_1") (pintype "passive"))
      (node (ref "R74") (pin "2") (pinfunction "2_2") (pintype "passive"))
      (node (ref "U10") (pin "C7") (pinfunction "XTALOUT_C7") (pintype "passive"))
    )
    (net (code "75") (name "Net-(CRY1-X2)") (class "Default")
      (node (ref "C118") (pin "2") (pinfunction "2_2") (pintype "passive"))
      (node (ref "CRY1") (pin "3") (pinfunction "X2_3") (pintype "passive"))
      (node (ref "R74") (pin "1") (pinfunction "1_1") (pintype "passive"))
      (node (ref "U10") (pin "C6") (pinfunction "XTALIN_C6") (pintype "passive"))
    )
    (net (code "76") (name "Net-(U10B-OTG_ID)") (class "Default")
      (node (ref "R57") (pin "2") (pinfunction "2_2") (pintype "passive"))
      (node (ref "U10") (pin "C9") (pinfunction "OTG_ID_C9") (pintype "passive"))
    )
    (net (code "77") (name "Net-(U10B-R_USB2)") (class "Default")
      (node (ref "R62") (pin "1") (pinfunction "1_1") (pintype "passive"))
      (node (ref "U10") (pin "C8") (pinfunction "R_USB2_C8") (pintype "passive"))
    )
    (net (code "78") (name "Net-(U10B-R_USB3)") (class "Default")
      (node (ref "R61") (pin "1") (pinfunction "1_1") (pintype "passive"))
      (node (ref "U10") (pin "B3") (pinfunction "R_USB3_B3") (pintype "passive"))
    )
    (net (code "79") (name "Net-(U11-IN)") (class "Default")
      (node (ref "P1") (pin "A4") (pinfunction "VBUS_A4") (pintype "passive"))
      (node (ref "P1") (pin "A9") (pinfunction "VBUS_A9") (pintype "passive"))
      (node (ref "P1") (pin "B4") (pinfunction "VBUS_B4") (pintype "passive"))
      (node (ref "P1") (pin "B9") (pinfunction "VBUS_B9") (pintype "passive"))
      (node (ref "U11") (pin "1") (pinfunction "IN_1") (pintype "passive"))
    )
    (net (code "80") (name "Net-(U13-OUT)") (class "Default")
      (node (ref "C116") (pin "1") (pinfunction "1_1") (pintype "passive"))
      (node (ref "R66") (pin "1") (pinfunction "1_1") (pintype "passive"))
      (node (ref "R67") (pin "2") (pinfunction "2_2") (pintype "passive"))
      (node (ref "U13") (pin "1") (pinfunction "OUT_1") (pintype "passive"))
    )
    (net (code "81") (name "Net-(U15-EN)") (class "Default")
      (node (ref "R70") (pin "1") (pinfunction "1_1") (pintype "passive"))
      (node (ref "U15") (pin "7") (pinfunction "VREF2_7") (pintype "passive"))
      (node (ref "U15") (pin "8") (pinfunction "EN_8") (pintype "passive"))
    )
    (net (code "82") (name "Net-(U16-WP)") (class "Default")
      (node (ref "R75") (pin "1") (pinfunction "1_1") (pintype "passive"))
      (node (ref "SJ2") (pin "2") (pinfunction "2_2") (pintype "passive"))
      (node (ref "U16") (pin "7") (pinfunction "WP_7") (pintype "input"))
    )
    (net (code "83") (name "Net-(U27-SEL)") (class "Default")
      (node (ref "R66") (pin "2") (pinfunction "2_2") (pintype "passive"))
      (node (ref "U27") (pin "9") (pinfunction "SEL_9") (pintype "passive"))
    )
    (net (code "84") (name "VCC1V0A_PLL") (class "Default")
      (node (ref "C122") (pin "2") (pinfunction "2_2") (pintype "passive"))
      (node (ref "C123") (pin "2") (pinfunction "2_2") (pintype "passive"))
      (node (ref "FB7") (pin "2") (pinfunction "2_2") (pintype "passive"))
      (node (ref "U10") (pin "A7") (pinfunction "AVDD_A7") (pintype "passive"))
    )
    (net (code "85") (name "VCC1V0A_USB") (class "Default")
      (node (ref "C124") (pin "2") (pinfunction "2_2") (pintype "passive"))
      (node (ref "C125") (pin "2") (pinfunction "2_2") (pintype "passive"))
      (node (ref "FB8") (pin "2") (pinfunction "2_2") (pintype "passive"))
      (node (ref "U10") (pin "A2") (pinfunction "U3RXVDDQ_A2") (pintype "passive"))
      (node (ref "U10") (pin "B5") (pinfunction "U3TXVDDQ_B5") (pintype "passive"))
    )
    (net (code "86") (name "VCC1V8") (class "Default")
      (node (ref "C119") (pin "1") (pinfunction "1_1") (pintype "passive"))
      (node (ref "C120") (pin "2") (pinfunction "2_2") (pintype "passive"))
      (node (ref "R71") (pin "1") (pinfunction "1_1") (pintype "passive"))
      (node (ref "R72") (pin "1") (pinfunction "1_1") (pintype "passive"))
      (node (ref "SJ2") (pin "1") (pinfunction "1_1") (pintype "passive"))
      (node (ref "U15") (pin "2") (pinfunction "VREF1_2") (pintype "passive"))
      (node (ref "U16") (pin "8") (pinfunction "Vcc_8") (pintype "power_in"))
    )
    (net (code "87") (name "VCC3V3") (class "Default")
      (node (ref "C112") (pin "2") (pinfunction "2_2") (pintype "passive"))
      (node (ref "C115") (pin "2") (pinfunction "2_2") (pintype "passive"))
      (node (ref "C128") (pin "2") (pinfunction "2_2") (pintype "passive"))
      (node (ref "C129") (pin "2") (pinfunction "2_2") (pintype "passive"))
      (node (ref "C130") (pin "2") (pinfunction "2_2") (pintype "passive"))
      (node (ref "C131") (pin "2") (pinfunction "2_2") (pintype "passive"))
      (node (ref "C132") (pin "2") (pinfunction "2_2") (pintype "passive"))
      (node (ref "C159") (pin "2") (pinfunction "2_2") (pintype "passive"))
      (node (ref "FB9") (pin "1") (pinfunction "1_1") (pintype "passive"))
      (node (ref "R59") (pin "1") (pinfunction "1_1") (pintype "passive"))
      (node (ref "R60") (pin "1") (pinfunction "1_1") (pintype "passive"))
      (node (ref "R67") (pin "1") (pinfunction "1_1") (pintype "passive"))
      (node (ref "R68") (pin "1") (pinfunction "1_1") (pintype "passive"))
      (node (ref "R69") (pin "1") (pinfunction "1_1") (pintype "passive"))
      (node (ref "R70") (pin "2") (pinfunction "2_2") (pintype "passive"))
      (node (ref "U10") (pin "B1") (pinfunction "VIO4_B1") (pintype "passive"))
      (node (ref "U10") (pin "C11") (pinfunction "VIO5_C11") (pintype "passive"))
      (node (ref "U10") (pin "E3") (pinfunction "VIO3_E3") (pintype "passive"))
      (node (ref "U10") (pin "F1") (pinfunction "VIO2_F1") (pintype "passive"))
      (node (ref "U10") (pin "H11") (pinfunction "VIO1_H11") (pintype "passive"))
      (node (ref "U10") (pin "H4") (pinfunction "PMODE[1]/GPIO[31]_H4") (pintype "passive"))
      (node (ref "U10") (pin "H7") (pinfunction "CTL[3]/SLRD#_H7") (pintype "passive"))
      (node (ref "U10") (pin "J7") (pinfunction "CTL[2]/SLOE#_J7") (pintype "passive"))
      (node (ref "U10") (pin "L9") (pinfunction "VIO1_L9") (pintype "passive"))
      (node (ref "U13") (pin "5") (pinfunction "VCC_5") (pintype "passive"))
      (node (ref "U14") (pin "3") (pinfunction "VCC_3") (pintype "passive"))
      (node (ref "U27") (pin "1") (pinfunction "VDD_1") (pintype "passive"))
      (node (ref "U27") (pin "10") (pinfunction "VDD_10") (pintype "passive"))
      (node (ref "U27") (pin "6") (pinfunction "VCC_6") (pintype "passive"))
    )
    (net (code "88") (name "VCC3V3IOUSB") (class "Default")
      (node (ref "C126") (pin "2") (pinfunction "2_2") (pintype "passive"))
      (node (ref "C127") (pin "2") (pinfunction "2_2") (pintype "passive"))
      (node (ref "FB9") (pin "2") (pinfunction "2_2") (pintype "passive"))
      (node (ref "U10") (pin "B6") (pinfunction "CVDDQ_B6") (pintype "passive"))
    )
    (net (code "89") (name "VCC5V") (class "Default")
      (node (ref "C110") (pin "2") (pinfunction "2_2") (pintype "passive"))
      (node (ref "ECP1") (pin "1") (pinfunction "1_1") (pintype "passive"))
      (node (ref "U10") (pin "E11") (pinfunction "VBUS_E11") (pintype "passive"))
      (node (ref "U11") (pin "5") (pinfunction "OUT_5") (pintype "passive"))
    )
    (net (code "90") (name "VCCFX3") (class "Default")
      (node (ref "C133") (pin "2") (pinfunction "2_2") (pintype "passive"))
      (node (ref "C134") (pin "2") (pinfunction "2_2") (pintype "passive"))
      (node (ref "C135") (pin "2") (pinfunction "2_2") (pintype "passive"))
      (node (ref "C136") (pin "2") (pinfunction "2_2") (pintype "passive"))
      (node (ref "C137") (pin "2") (pinfunction "2_2") (pintype "passive"))
      (node (ref "FB7") (pin "1") (pinfunction "1_1") (pintype "passive"))
      (node (ref "FB8") (pin "1") (pinfunction "1_1") (pintype "passive"))
      (node (ref "R76") (pin "1") (pinfunction "1_1") (pintype "passive"))
      (node (ref "R77") (pin "1") (pinfunction "1_1") (pintype "passive"))
      (node (ref "U10") (pin "B10") (pinfunction "VDD_B10") (pintype "passive"))
      (node (ref "U10") (pin "C3") (pinfunction "VDD_C3") (pintype "passive"))
      (node (ref "U10") (pin "E9") (pinfunction "VDD_E9") (pintype "passive"))
      (node (ref "U10") (pin "F11") (pinfunction "VDD_F11") (pintype "passive"))
      (node (ref "U10") (pin "H1") (pinfunction "VDD_H1") (pintype "passive"))
      (node (ref "U10") (pin "J11") (pinfunction "VDD_J11") (pintype "passive"))
      (node (ref "U10") (pin "L5") (pinfunction "VDD_L5") (pintype "passive"))
      (node (ref "U10") (pin "L7") (pinfunction "VDD_L7") (pintype "passive"))
    )
    (net (code "91") (name "unconnected-(CRY1-NC-Pad2)") (class "Default")
      (node (ref "CRY1") (pin "2") (pinfunction "NC_2") (pintype "passive"))
    )
    (net (code "92") (name "unconnected-(CRY1-NC-Pad4)") (class "Default")
      (node (ref "CRY1") (pin "4") (pinfunction "NC_4") (pintype "passive"))
    )
    (net (code "93") (name "unconnected-(P1-SBU1-PadA8)") (class "Default")
      (node (ref "P1") (pin "A8") (pinfunction "SBU1_A8") (pintype "passive+no_connect"))
    )
    (net (code "94") (name "unconnected-(P1-SBU2-PadB8)") (class "Default")
      (node (ref "P1") (pin "B8") (pinfunction "SBU2_B8") (pintype "passive+no_connect"))
    )
    (net (code "95") (name "unconnected-(U1N-REF_RES_4A-PadV11)") (class "Default")
      (node (ref "U1") (pin "V11") (pinfunction "REF_RES_4A_V11") (pintype "power_in+no_connect"))
    )
    (net (code "96") (name "unconnected-(U1O-REF_RES_4B-PadV17)") (class "Default")
      (node (ref "U1") (pin "V17") (pinfunction "REF_RES_4B_V17") (pintype "power_in+no_connect"))
    )
    (net (code "97") (name "unconnected-(U10A-CTL[8]{slash}GPIO-PadG5)") (class "Default")
      (node (ref "U10") (pin "G5") (pinfunction "CTL[8]/GPIO_G5") (pintype "passive+no_connect"))
    )
    (net (code "98") (name "unconnected-(U10A-CTL[9]{slash}GPIO-PadH6)") (class "Default")
      (node (ref "U10") (pin "H6") (pinfunction "CTL[9]/GPIO_H6") (pintype "passive+no_connect"))
    )
    (net (code "99") (name "unconnected-(U10A-CTL[10]{slash}GPIO-PadK5)") (class "Default")
      (node (ref "U10") (pin "K5") (pinfunction "CTL[10]/GPIO_K5") (pintype "passive+no_connect"))
    )
    (net (code "100") (name "unconnected-(U10A-GPIO[45]-PadF2)") (class "Default")
      (node (ref "U10") (pin "F2") (pinfunction "GPIO[45]_F2") (pintype "passive"))
    )
    (net (code "101") (name "unconnected-(U10A-I2S_CLK{slash}GPIO[50]-PadD1)") (class "Default")
      (node (ref "U10") (pin "D1") (pinfunction "I2S_CLK/GPIO[50]_D1") (pintype "passive"))
    )
    (net (code "102") (name "unconnected-(U10A-I2S_MCLK{slash}GPIO-PadC4)") (class "Default")
      (node (ref "U10") (pin "C4") (pinfunction "I2S_MCLK/GPIO_C4") (pintype "passive"))
    )
    (net (code "103") (name "unconnected-(U10A-I2S_SD{slash}GPIO[51]-PadD2)") (class "Default")
      (node (ref "U10") (pin "D2") (pinfunction "I2S_SD/GPIO[51]_D2") (pintype "passive"))
    )
    (net (code "104") (name "unconnected-(U10A-I2S_WS{slash}GPIO[52]-PadD3)") (class "Default")
      (node (ref "U10") (pin "D3") (pinfunction "I2S_WS/GPIO[52]_D3") (pintype "passive"))
    )
    (net (code "105") (name "unconnected-(U10A-INT#{slash}CTL[15]-PadL8)") (class "Default")
      (node (ref "U10") (pin "L8") (pinfunction "INT#/CTL[15]_L8") (pintype "passive"))
    )
    (net (code "106") (name "unconnected-(U10A-PMODE[0]{slash}GPIO[30]-PadG4)") (class "Default")
      (node (ref "U10") (pin "G4") (pinfunction "PMODE[0]/GPIO[30]_G4") (pintype "passive"))
    )
    (net (code "107") (name "unconnected-(U10A-PMODE[2]{slash}GPIO[32]-PadL4)") (class "Default")
      (node (ref "U10") (pin "L4") (pinfunction "PMODE[2]/GPIO[32]_L4") (pintype "passive+no_connect"))
    )
    (net (code "108") (name "unconnected-(U10C-CLKIN-PadD7)") (class "Default")
      (node (ref "U10") (pin "D7") (pinfunction "CLKIN_D7") (pintype "passive"))
    )
    (net (code "109") (name "unconnected-(U10C-CLKIN_32-PadD6)") (class "Default")
      (node (ref "U10") (pin "D6") (pinfunction "CLKIN_32_D6") (pintype "passive"))
    )
    (net (code "110") (name "unconnected-(U10C-TCK-PadF6)") (class "Default")
      (node (ref "U10") (pin "F6") (pinfunction "TCK_F6") (pintype "passive+no_connect"))
    )
    (net (code "111") (name "unconnected-(U10C-TDI-PadE7)") (class "Default")
      (node (ref "U10") (pin "E7") (pinfunction "TDI_E7") (pintype "passive+no_connect"))
    )
    (net (code "112") (name "unconnected-(U10C-TDO-PadC10)") (class "Default")
      (node (ref "U10") (pin "C10") (pinfunction "TDO_C10") (pintype "passive+no_connect"))
    )
    (net (code "113") (name "unconnected-(U10C-TMS-PadE8)") (class "Default")
      (node (ref "U10") (pin "E8") (pinfunction "TMS_E8") (pintype "passive+no_connect"))
    )
    (net (code "114") (name "unconnected-(U10C-TRST#-PadB11)") (class "Default")
      (node (ref "U10") (pin "B11") (pinfunction "TRST#_B11") (pintype "passive+no_connect"))
    )
    (net (code "115") (name "unconnected-(U11-FLAG-Pad4)") (class "Default")
      (node (ref "U11") (pin "4") (pinfunction "FLAG_4") (pintype "passive+no_connect"))
    )
  )
)
